# design.net
KiCad netlist of a schematic drawn in Altium Designer
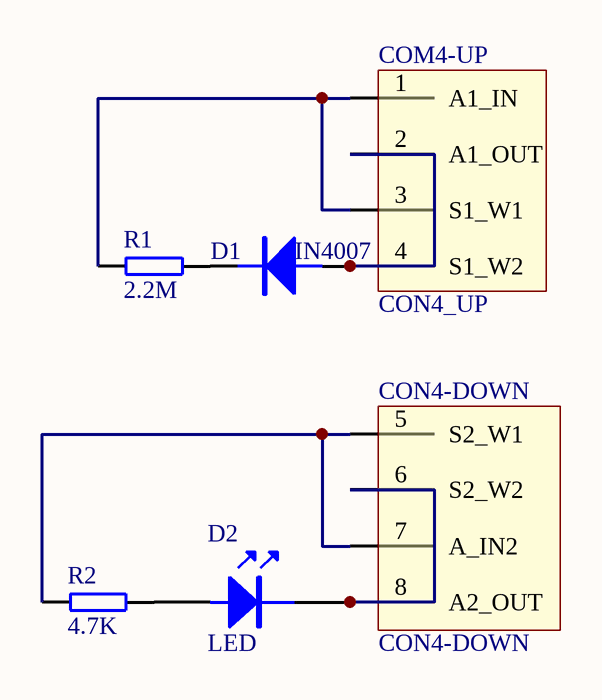
[diagram p0: 虚拟离子电流.SchDoc]

(export (version "E")
  (design (tool "Eeschema 10.0.6"))
  (components
    (comp (ref "COM4-UP") (value "CON4_UP") (footprint "CON4_UP") (libsource (lib "虚拟离子电流") (part "CON4_UP")))
    (comp (ref "CON4-DOWN")
      (value "CON4-DOWN")
      (footprint "CON4_DOWN")
      (libsource (lib "虚拟离子电流") (part "CON4-DOWN"))
    )
    (comp (ref "D1")
      (value "IN4007")
      (footprint "D")
      (description "Diode")
      (libsource (lib "*") (part "DIODE"))
    )
    (comp (ref "D2") (value "LED") (footprint "LED") (libsource (lib "*") (part "LED")))
    (comp (ref "R1") (value "2.2M") (footprint "R") (libsource (lib "*") (part "RES2")))
    (comp (ref "R2") (value "4.7K") (footprint "R") (libsource (lib "*") (part "RES2")))
  )
  (nets
    (net (code "1") (name "Net-(COM4-UP-A1_IN)") (class "Default")
      (node (ref "COM4-UP") (pin "1") (pinfunction "A1_IN_1") (pintype "passive"))
      (node (ref "COM4-UP") (pin "3") (pinfunction "S1_W1_3") (pintype "passive"))
      (node (ref "R1") (pin "1") (pinfunction "1_1") (pintype "passive"))
    )
    (net (code "2") (name "Net-(COM4-UP-A1_OUT)") (class "Default")
      (node (ref "COM4-UP") (pin "2") (pinfunction "A1_OUT_2") (pintype "passive"))
      (node (ref "COM4-UP") (pin "4") (pinfunction "S1_W2_4") (pintype "passive"))
      (node (ref "D1") (pin "1") (pinfunction "1_1") (pintype "passive"))
    )
    (net (code "3") (name "Net-(CON4-DOWN-A2_OUT)") (class "Default")
      (node (ref "CON4-DOWN") (pin "6") (pinfunction "S2_W2_6") (pintype "passive"))
      (node (ref "CON4-DOWN") (pin "8") (pinfunction "A2_OUT_8") (pintype "passive"))
      (node (ref "D2") (pin "K") (pinfunction "2_K") (pintype "passive"))
    )
    (net (code "4") (name "Net-(CON4-DOWN-A_IN2)") (class "Default")
      (node (ref "CON4-DOWN") (pin "5") (pinfunction "S2_W1_5") (pintype "passive"))
      (node (ref "CON4-DOWN") (pin "7") (pinfunction "A_IN2_7") (pintype "passive"))
      (node (ref "R2") (pin "1") (pinfunction "1_1") (pintype "passive"))
    )
    (net (code "5") (name "Net-(D1-Pad2)") (class "Default")
      (node (ref "D1") (pin "2") (pinfunction "2_2") (pintype "passive"))
      (node (ref "R1") (pin "2") (pinfunction "2_2") (pintype "passive"))
    )
    (net (code "6") (name "Net-(D2-1)") (class "Default")
      (node (ref "D2") (pin "A") (pinfunction "1_A") (pintype "passive"))
      (node (ref "R2") (pin "2") (pinfunction "2_2") (pintype "passive"))
    )
  )
)
